# USB_Hub.net
KiCad netlist of a schematic drawn in Altium Designer
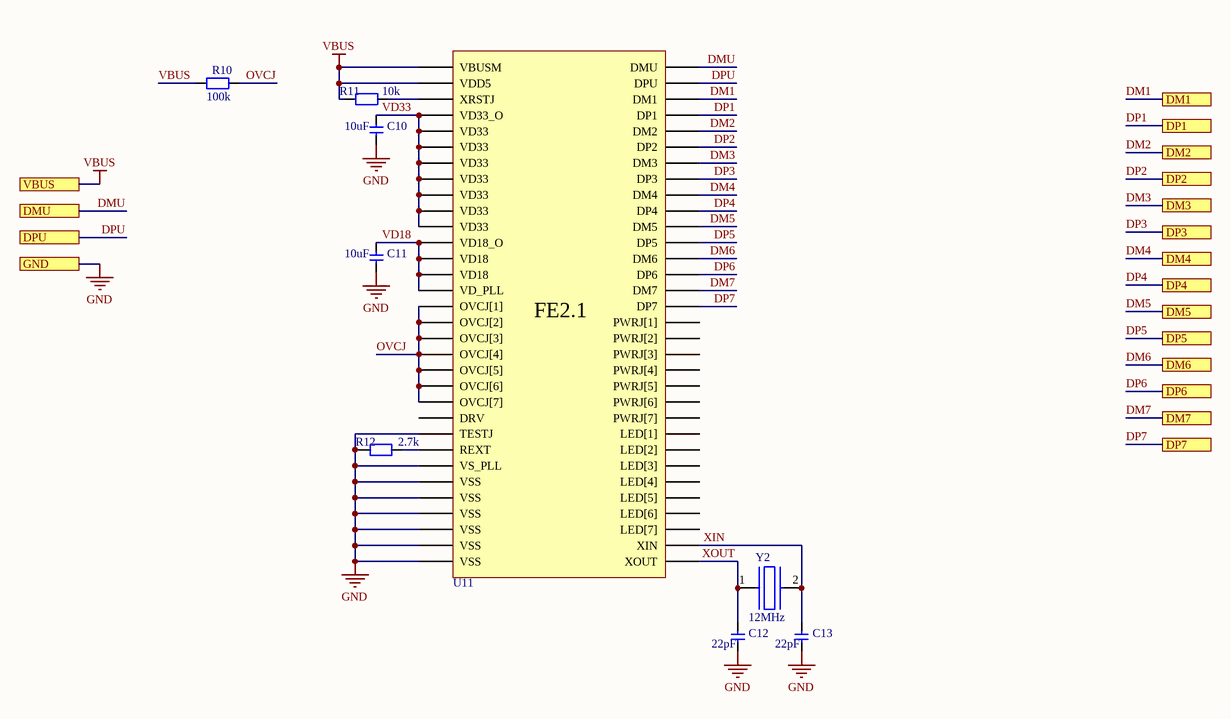
[diagram p0: USB Hub.SchDoc]

(export (version "E")
  (design (tool "Eeschema 10.0.6"))
  (components
    (comp (ref "C10")
      (value "10uF")
      (footprint "cap0603")
      (libsource (lib "AlexChistiakov") (part "Cap SMD"))
    )
    (comp (ref "C11")
      (value "10uF")
      (footprint "cap0603")
      (libsource (lib "AlexChistiakov") (part "Cap SMD"))
    )
    (comp (ref "C12")
      (value "22pF")
      (footprint "cap0603")
      (libsource (lib "AlexChistiakov") (part "Cap SMD"))
    )
    (comp (ref "C13")
      (value "22pF")
      (footprint "cap0603")
      (libsource (lib "AlexChistiakov") (part "Cap SMD"))
    )
    (comp (ref "R10")
      (value "100k")
      (footprint "res0603")
      (libsource (lib "AlexChistiakov") (part "Resistor SMD"))
    )
    (comp (ref "R11")
      (value "10k")
      (footprint "res0603")
      (libsource (lib "AlexChistiakov") (part "Resistor SMD"))
    )
    (comp (ref "R12")
      (value "2.7k")
      (footprint "res0603")
      (libsource (lib "AlexChistiakov") (part "Resistor SMD"))
    )
    (comp (ref "U11")
      (value "FE2.1")
      (footprint "LQFP64_N_1")
      (libsource (lib "AlexChistiakov") (part "FE2.1"))
    )
    (comp (ref "Y2")
      (value "12MHz")
      (footprint "QSMD5.0x3.2x1.0")
      (libsource (lib "AlexChistiakov") (part "Quartz"))
    )
  )
  (nets
    (net (code "1") (name "/DM1") (class "Default")
      (node (ref "U11") (pin "26") (pinfunction "DM1_26") (pintype "passive"))
    )
    (net (code "2") (name "/DM2") (class "Default")
      (node (ref "U11") (pin "23") (pinfunction "DM2_23") (pintype "passive"))
    )
    (net (code "3") (name "/DM3") (class "Default")
      (node (ref "U11") (pin "20") (pinfunction "DM3_20") (pintype "passive"))
    )
    (net (code "4") (name "/DM4") (class "Default")
      (node (ref "U11") (pin "17") (pinfunction "DM4_17") (pintype "passive"))
    )
    (net (code "5") (name "/DM5") (class "Default")
      (node (ref "U11") (pin "41") (pinfunction "DM5_41") (pintype "passive"))
    )
    (net (code "6") (name "/DM6") (class "Default")
      (node (ref "U11") (pin "44") (pinfunction "DM6_44") (pintype "passive"))
    )
    (net (code "7") (name "/DM7") (class "Default")
      (node (ref "U11") (pin "47") (pinfunction "DM7_47") (pintype "passive"))
    )
    (net (code "8") (name "/DMU") (class "Default")
      (node (ref "U11") (pin "38") (pinfunction "DMU_38") (pintype "passive"))
    )
    (net (code "9") (name "/DP1") (class "Default")
      (node (ref "U11") (pin "27") (pinfunction "DP1_27") (pintype "passive"))
    )
    (net (code "10") (name "/DP2") (class "Default")
      (node (ref "U11") (pin "24") (pinfunction "DP2_24") (pintype "passive"))
    )
    (net (code "11") (name "/DP3") (class "Default")
      (node (ref "U11") (pin "21") (pinfunction "DP3_21") (pintype "passive"))
    )
    (net (code "12") (name "/DP4") (class "Default")
      (node (ref "U11") (pin "18") (pinfunction "DP4_18") (pintype "passive"))
    )
    (net (code "13") (name "/DP5") (class "Default")
      (node (ref "U11") (pin "42") (pinfunction "DP5_42") (pintype "passive"))
    )
    (net (code "14") (name "/DP6") (class "Default")
      (node (ref "U11") (pin "45") (pinfunction "DP6_45") (pintype "passive"))
    )
    (net (code "15") (name "/DP7") (class "Default")
      (node (ref "U11") (pin "48") (pinfunction "DP7_48") (pintype "passive"))
    )
    (net (code "16") (name "/DPU") (class "Default")
      (node (ref "U11") (pin "39") (pinfunction "DPU_39") (pintype "passive"))
    )
    (net (code "17") (name "/OVCJ") (class "Default")
      (node (ref "R10") (pin "2") (pinfunction "2_2") (pintype "passive"))
      (node (ref "U11") (pin "14") (pinfunction "OVCJ[1]_14") (pintype "passive"))
      (node (ref "U11") (pin "15") (pinfunction "OVCJ[2]_15") (pintype "passive"))
      (node (ref "U11") (pin "16") (pinfunction "OVCJ[3]_16") (pintype "passive"))
      (node (ref "U11") (pin "17") (pinfunction "OVCJ[4]_17") (pintype "passive"))
      (node (ref "U11") (pin "18") (pinfunction "OVCJ[5]_18") (pintype "passive"))
      (node (ref "U11") (pin "19") (pinfunction "OVCJ[6]_19") (pintype "passive"))
      (node (ref "U11") (pin "20") (pinfunction "OVCJ[7]_20") (pintype "passive"))
    )
    (net (code "18") (name "/VD18") (class "Default")
      (node (ref "C11") (pin "2") (pinfunction "2_2") (pintype "passive"))
      (node (ref "U11") (pin "29") (pinfunction "VD_PLL_29") (pintype "passive"))
      (node (ref "U11") (pin "33") (pinfunction "VD18_O_33") (pintype "passive"))
      (node (ref "U11") (pin "36") (pinfunction "VD18_36") (pintype "passive"))
      (node (ref "U11") (pin "7") (pinfunction "VD18_7") (pintype "passive"))
    )
    (net (code "19") (name "/VD33") (class "Default")
      (node (ref "C10") (pin "2") (pinfunction "2_2") (pintype "passive"))
      (node (ref "U11") (pin "10") (pinfunction "VD33_O_10") (pintype "passive"))
      (node (ref "U11") (pin "16") (pinfunction "VD33_16") (pintype "passive"))
      (node (ref "U11") (pin "22") (pinfunction "VD33_22") (pintype "passive"))
      (node (ref "U11") (pin "28") (pinfunction "VD33_28") (pintype "passive"))
      (node (ref "U11") (pin "34") (pinfunction "VD33_34") (pintype "passive"))
      (node (ref "U11") (pin "40") (pinfunction "VD33_40") (pintype "passive"))
      (node (ref "U11") (pin "46") (pinfunction "VD33_46") (pintype "passive"))
      (node (ref "U11") (pin "56") (pinfunction "VD33_56") (pintype "passive"))
    )
    (net (code "20") (name "/XIN") (class "Default")
      (node (ref "C13") (pin "2") (pinfunction "2_2") (pintype "passive"))
      (node (ref "U11") (pin "30") (pinfunction "XIN_30") (pintype "passive"))
      (node (ref "Y2") (pin "2") (pintype "power_in"))
    )
    (net (code "21") (name "/XOUT") (class "Default")
      (node (ref "C12") (pin "2") (pinfunction "2_2") (pintype "passive"))
      (node (ref "U11") (pin "31") (pinfunction "XOUT_31") (pintype "passive"))
      (node (ref "Y2") (pin "1") (pintype "power_in"))
    )
    (net (code "22") (name "GND") (class "Default")
      (node (ref "C10") (pin "1") (pinfunction "1_1") (pintype "passive"))
      (node (ref "C11") (pin "1") (pinfunction "1_1") (pintype "passive"))
      (node (ref "C12") (pin "1") (pinfunction "1_1") (pintype "passive"))
      (node (ref "C13") (pin "1") (pinfunction "1_1") (pintype "passive"))
      (node (ref "R12") (pin "1") (pinfunction "1_1") (pintype "passive"))
      (node (ref "U11") (pin "11") (pinfunction "VSS_11") (pintype "passive"))
      (node (ref "U11") (pin "19") (pinfunction "VSS_19") (pintype "passive"))
      (node (ref "U11") (pin "25") (pinfunction "VSS_25") (pintype "passive"))
      (node (ref "U11") (pin "3") (pinfunction "TESTJ_3") (pintype "passive"))
      (node (ref "U11") (pin "32") (pinfunction "VS_PLL_32") (pintype "passive"))
      (node (ref "U11") (pin "37") (pinfunction "VSS_37") (pintype "passive"))
      (node (ref "U11") (pin "43") (pinfunction "VSS_43") (pintype "passive"))
      (node (ref "U11") (pin "49") (pinfunction "VSS_49") (pintype "passive"))
    )
    (net (code "23") (name "Net-(U11-REXT)") (class "Default")
      (node (ref "R12") (pin "2") (pinfunction "2_2") (pintype "passive"))
      (node (ref "U11") (pin "35") (pinfunction "REXT_35") (pintype "passive"))
    )
    (net (code "24") (name "Net-(U11-XRSTJ)") (class "Default")
      (node (ref "R11") (pin "2") (pinfunction "2_2") (pintype "passive"))
      (node (ref "U11") (pin "50") (pinfunction "XRSTJ_50") (pintype "passive"))
    )
    (net (code "25") (name "VBUS") (class "Default")
      (node (ref "R10") (pin "1") (pinfunction "1_1") (pintype "passive"))
      (node (ref "R11") (pin "1") (pinfunction "1_1") (pintype "passive"))
      (node (ref "U11") (pin "51") (pinfunction "VBUSM_51") (pintype "passive"))
      (node (ref "U11") (pin "9") (pinfunction "VDD5_9") (pintype "passive"))
    )
    (net (code "26") (name "unconnected-(U11-DRV-Pad2)") (class "Default")
      (node (ref "U11") (pin "2") (pinfunction "DRV_2") (pintype "passive"))
    )
    (net (code "27") (name "unconnected-(U11-LED[1]-Pad4)") (class "Default")
      (node (ref "U11") (pin "4") (pinfunction "LED[1]_4") (pintype "passive"))
    )
    (net (code "28") (name "unconnected-(U11-LED[2]-Pad5)") (class "Default")
      (node (ref "U11") (pin "5") (pinfunction "LED[2]_5") (pintype "passive"))
    )
    (net (code "29") (name "unconnected-(U11-LED[3]-Pad6)") (class "Default")
      (node (ref "U11") (pin "6") (pinfunction "LED[3]_6") (pintype "passive"))
    )
    (net (code "30") (name "unconnected-(U11-LED[4]-Pad8)") (class "Default")
      (node (ref "U11") (pin "8") (pinfunction "LED[4]_8") (pintype "passive"))
    )
    (net (code "31") (name "unconnected-(U11-LED[5]-Pad1)") (class "Default")
      (node (ref "U11") (pin "1") (pinfunction "LED[5]_1") (pintype "passive"))
    )
    (net (code "32") (name "unconnected-(U11-LED[6]-Pad64)") (class "Default")
      (node (ref "U11") (pin "64") (pinfunction "LED[6]_64") (pintype "passive"))
    )
    (net (code "33") (name "unconnected-(U11-LED[7]-Pad63)") (class "Default")
      (node (ref "U11") (pin "63") (pinfunction "LED[7]_63") (pintype "passive"))
    )
    (net (code "34") (name "unconnected-(U11-PWRJ[1]-Pad59)") (class "Default")
      (node (ref "U11") (pin "59") (pinfunction "PWRJ[1]_59") (pintype "passive"))
    )
    (net (code "35") (name "unconnected-(U11-PWRJ[2]-Pad61)") (class "Default")
      (node (ref "U11") (pin "61") (pinfunction "PWRJ[2]_61") (pintype "passive"))
    )
    (net (code "36") (name "unconnected-(U11-PWRJ[3]-Pad12)") (class "Default")
      (node (ref "U11") (pin "12") (pinfunction "PWRJ[3]_12") (pintype "passive"))
    )
    (net (code "37") (name "unconnected-(U11-PWRJ[4]-Pad14)") (class "Default")
      (node (ref "U11") (pin "14") (pinfunction "PWRJ[4]_14") (pintype "passive"))
    )
    (net (code "38") (name "unconnected-(U11-PWRJ[5]-Pad57)") (class "Default")
      (node (ref "U11") (pin "57") (pinfunction "PWRJ[5]_57") (pintype "passive"))
    )
    (net (code "39") (name "unconnected-(U11-PWRJ[6]-Pad54)") (class "Default")
      (node (ref "U11") (pin "54") (pinfunction "PWRJ[6]_54") (pintype "passive"))
    )
    (net (code "40") (name "unconnected-(U11-PWRJ[7]-Pad52)") (class "Default")
      (node (ref "U11") (pin "52") (pinfunction "PWRJ[7]_52") (pintype "passive"))
    )
  )
)
